# main.net
KiCad netlist of a schematic drawn in Altium Designer
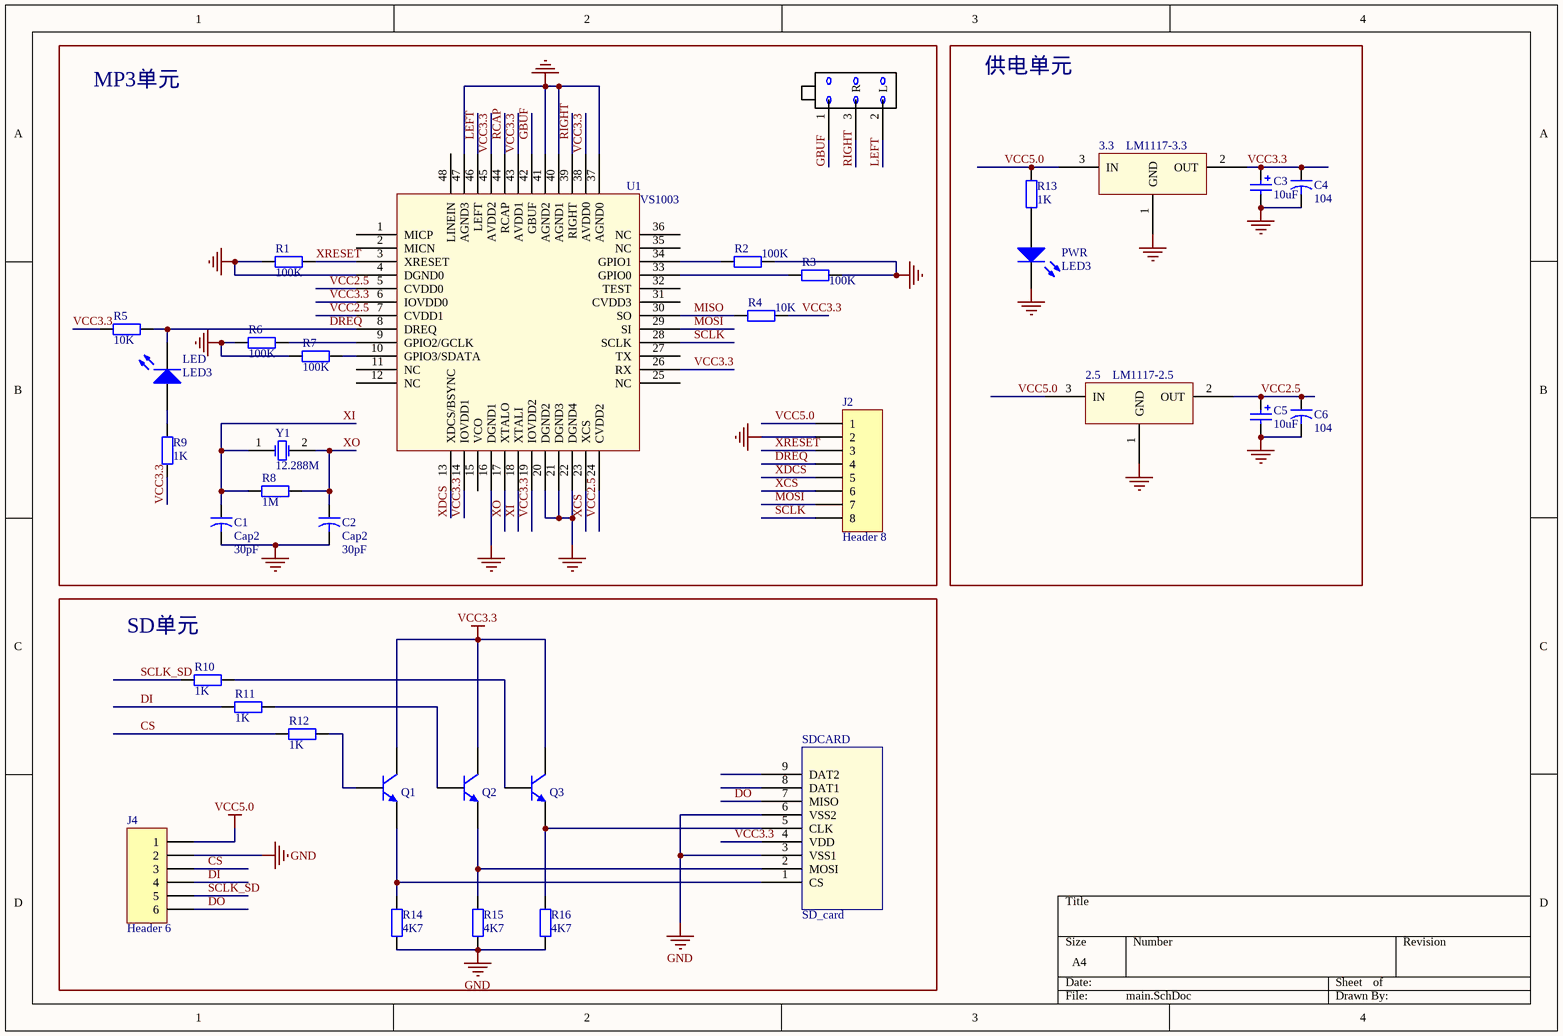
[diagram p0: main.SchDoc]

(export (version "E")
  (design (tool "Eeschema 10.0.6"))
  (components
    (comp (ref "2.5") (value "LM1117-2.5") (footprint "SOT223") (libsource (lib "kkk") (part "LM1117-3.3")))
    (comp (ref "3.3") (value "LM1117-3.3") (footprint "SOT223") (libsource (lib "kkk") (part "LM1117-3.3")))
    (comp (ref "C1")
      (value "Cap2")
      (footprint "C0805")
      (description "Capacitor")
      (fields (field (name "ALTIUM_VALUE") "30pF") (field (name "PUBLISHER") "Altium Limited"))
      (libsource (lib "Miscellaneous Devices") (part "Cap2"))
    )
    (comp (ref "C2")
      (value "Cap2")
      (footprint "C0805")
      (description "Capacitor")
      (fields (field (name "ALTIUM_VALUE") "30pF") (field (name "PUBLISHER") "Altium Limited"))
      (libsource (lib "Miscellaneous Devices") (part "Cap2"))
    )
    (comp (ref "C3")
      (value "10uF")
      (footprint "3528")
      (description "Polarized Capacitor (Surface Mount)")
      (fields (field (name "Comment") "Cap Pol3") (field (name "PUBLISHER") "Altium Limited"))
      (libsource (lib "Miscellaneous Devices") (part "Cap Pol3"))
    )
    (comp (ref "C4")
      (value "104")
      (footprint "C0805")
      (description "Capacitor")
      (fields (field (name "Comment") "Cap2") (field (name "PUBLISHER") "Altium Limited"))
      (libsource (lib "Miscellaneous Devices") (part "Cap2"))
    )
    (comp (ref "C5")
      (value "10uF")
      (footprint "3528")
      (description "Polarized Capacitor (Surface Mount)")
      (fields (field (name "Comment") "Cap Pol3") (field (name "PUBLISHER") "Altium Limited"))
      (libsource (lib "Miscellaneous Devices") (part "Cap Pol3"))
    )
    (comp (ref "C6")
      (value "104")
      (footprint "C0805")
      (description "Capacitor")
      (fields (field (name "Comment") "Cap2") (field (name "PUBLISHER") "Altium Limited"))
      (libsource (lib "Miscellaneous Devices") (part "Cap2"))
    )
    (comp (ref "J2")
      (value "Header 8")
      (footprint "HDR1X8")
      (description "Header, 8-Pin")
      (fields (field (name "PUBLISHER") "Altium Limited"))
      (libsource (lib "Miscellaneous Connectors") (part "Header 8"))
    )
    (comp (ref "J4")
      (value "Header 6")
      (footprint "HDR1X6")
      (description "Header, 6-Pin")
      (fields (field (name "PUBLISHER") "Altium Limited"))
      (libsource (lib "Miscellaneous Connectors") (part "Header 6"))
    )
    (comp (ref "LED")
      (value "LED3")
      (footprint "DSO-C2/D5.6")
      (description "Typical BLUE SiC LED")
      (fields (field (name "PUBLISHER") "Altium Limited"))
      (libsource (lib "Miscellaneous Devices") (part "LED3"))
    )
    (comp (ref "Phonejack")
      (value "Phonejack")
      (footprint "3.5mmphonejack")
      (libsource (lib "MyLib") (part "Phonejack"))
    )
    (comp (ref "PWR")
      (value "LED3")
      (footprint "DSO-C2/D5.6")
      (description "Typical BLUE SiC LED")
      (fields (field (name "PUBLISHER") "Altium Limited"))
      (libsource (lib "Miscellaneous Devices") (part "LED3"))
    )
    (comp (ref "Q1") (value "8050") (footprint "SOT-23") (libsource (lib "MyLib") (part "8050")))
    (comp (ref "Q2") (value "8050") (footprint "SOT-23") (libsource (lib "MyLib") (part "8050")))
    (comp (ref "Q3") (value "8050") (footprint "SOT-23") (libsource (lib "MyLib") (part "8050")))
    (comp (ref "R1")
      (value "100K")
      (footprint "C0805")
      (description "Resistor")
      (fields (field (name "Comment") "Res2") (field (name "PUBLISHER") "Altium Limited"))
      (libsource (lib "Miscellaneous Devices") (part "Res2"))
    )
    (comp (ref "R2")
      (value "100K")
      (footprint "C0805")
      (description "Resistor")
      (fields (field (name "Comment") "Res2") (field (name "PUBLISHER") "Altium Limited"))
      (libsource (lib "Miscellaneous Devices") (part "Res2"))
    )
    (comp (ref "R3")
      (value "100K")
      (footprint "C0805")
      (description "Resistor")
      (fields (field (name "Comment") "Res2") (field (name "PUBLISHER") "Altium Limited"))
      (libsource (lib "Miscellaneous Devices") (part "Res2"))
    )
    (comp (ref "R4")
      (value "10K")
      (footprint "C0805")
      (description "Resistor")
      (fields (field (name "Comment") "Res2") (field (name "PUBLISHER") "Altium Limited"))
      (libsource (lib "Miscellaneous Devices") (part "Res2"))
    )
    (comp (ref "R5")
      (value "10K")
      (footprint "C0805")
      (description "Resistor")
      (fields (field (name "Comment") "Res2") (field (name "PUBLISHER") "Altium Limited"))
      (libsource (lib "Miscellaneous Devices") (part "Res2"))
    )
    (comp (ref "R6")
      (value "100K")
      (footprint "C0805")
      (description "Resistor")
      (fields (field (name "Comment") "Res2") (field (name "PUBLISHER") "Altium Limited"))
      (libsource (lib "Miscellaneous Devices") (part "Res2"))
    )
    (comp (ref "R7")
      (value "100K")
      (footprint "C0805")
      (description "Resistor")
      (fields (field (name "Comment") "Res2") (field (name "PUBLISHER") "Altium Limited"))
      (libsource (lib "Miscellaneous Devices") (part "Res2"))
    )
    (comp (ref "R8")
      (value "1M")
      (footprint "C0805")
      (description "Resistor")
      (fields (field (name "Comment") "Res2") (field (name "PUBLISHER") "Altium Limited"))
      (libsource (lib "Miscellaneous Devices") (part "Res2"))
    )
    (comp (ref "R9")
      (value "1K")
      (footprint "C0805")
      (description "Resistor")
      (fields (field (name "Comment") "Res2") (field (name "PUBLISHER") "Altium Limited"))
      (libsource (lib "") (part "Res2_2"))
    )
    (comp (ref "R10")
      (value "1K")
      (footprint "C0805")
      (description "Resistor")
      (fields (field (name "Comment") "Res2") (field (name "PUBLISHER") "Altium Limited"))
      (libsource (lib "") (part "Res2_3"))
    )
    (comp (ref "R11")
      (value "1K")
      (footprint "C0805")
      (description "Resistor")
      (fields (field (name "Comment") "Res2") (field (name "PUBLISHER") "Altium Limited"))
      (libsource (lib "") (part "Res2_3"))
    )
    (comp (ref "R12")
      (value "1K")
      (footprint "C0805")
      (description "Resistor")
      (fields (field (name "Comment") "Res2") (field (name "PUBLISHER") "Altium Limited"))
      (libsource (lib "") (part "Res2_3"))
    )
    (comp (ref "R13")
      (value "1K")
      (footprint "C0805")
      (description "Resistor")
      (fields (field (name "Comment") "Res2") (field (name "PUBLISHER") "Altium Limited"))
      (libsource (lib "") (part "Res2_4"))
    )
    (comp (ref "R14")
      (value "4K7")
      (footprint "C0805")
      (description "Resistor")
      (fields (field (name "Comment") "Res2") (field (name "PUBLISHER") "Altium Limited"))
      (libsource (lib "") (part "Res2_1"))
    )
    (comp (ref "R15")
      (value "4K7")
      (footprint "C0805")
      (description "Resistor")
      (fields (field (name "Comment") "Res2") (field (name "PUBLISHER") "Altium Limited"))
      (libsource (lib "") (part "Res2_1"))
    )
    (comp (ref "R16")
      (value "4K7")
      (footprint "C0805")
      (description "Resistor")
      (fields (field (name "Comment") "Res2") (field (name "PUBLISHER") "Altium Limited"))
      (libsource (lib "") (part "Res2_1"))
    )
    (comp (ref "SDCARD") (value "SD_card") (footprint "SDCARD") (libsource (lib "kkk") (part "SD_card")))
    (comp (ref "U1") (value "VS1003") (footprint "LQFP-48") (libsource (lib "kkk") (part "VS1003")))
    (comp (ref "Y1")
      (value "12.288M")
      (footprint "XTAL")
      (description "Crystal Oscillator")
      (fields (field (name "PUBLISHER") "Altium Limited"))
      (libsource (lib "Miscellaneous Devices") (part "XTAL"))
    )
  )
  (nets
    (net (code "1") (name "/CS") (class "Default")
      (node (ref "J4") (pin "3") (pinfunction "3_3") (pintype "passive"))
      (node (ref "R12") (pin "1") (pinfunction "1_1") (pintype "passive"))
    )
    (net (code "2") (name "/DI") (class "Default")
      (node (ref "J4") (pin "4") (pinfunction "4_4") (pintype "passive"))
      (node (ref "R11") (pin "1") (pinfunction "1_1") (pintype "passive"))
    )
    (net (code "3") (name "/DO") (class "Default")
      (node (ref "J4") (pin "6") (pinfunction "6_6") (pintype "passive"))
      (node (ref "SDCARD") (pin "7") (pinfunction "MISO_7") (pintype "power_in"))
    )
    (net (code "4") (name "/DREQ") (class "Default")
      (node (ref "J2") (pin "4") (pinfunction "4_4") (pintype "passive"))
      (node (ref "LED") (pin "2") (pinfunction "K_2") (pintype "passive"))
      (node (ref "R5") (pin "2") (pinfunction "2_2") (pintype "passive"))
      (node (ref "U1") (pin "8") (pinfunction "DREQ_8") (pintype "passive"))
    )
    (net (code "5") (name "/GBUF") (class "Default")
      (node (ref "Phonejack") (pin "1") (pinfunction "GBUF_1") (pintype "passive"))
      (node (ref "U1") (pin "42") (pinfunction "GBUF_42") (pintype "passive"))
    )
    (net (code "6") (name "/LEFT") (class "Default")
      (node (ref "Phonejack") (pin "2") (pinfunction "L_2") (pintype "passive"))
      (node (ref "U1") (pin "46") (pinfunction "LEFT_46") (pintype "passive"))
    )
    (net (code "7") (name "/MISO") (class "Default")
      (node (ref "R4") (pin "1") (pinfunction "1_1") (pintype "passive"))
      (node (ref "U1") (pin "30") (pinfunction "SO_30") (pintype "passive"))
    )
    (net (code "8") (name "/MOSI") (class "Default")
      (node (ref "J2") (pin "7") (pinfunction "7_7") (pintype "passive"))
      (node (ref "U1") (pin "29") (pinfunction "SI_29") (pintype "passive"))
    )
    (net (code "9") (name "/RCAP") (class "Default")
      (node (ref "U1") (pin "44") (pinfunction "RCAP_44") (pintype "passive"))
    )
    (net (code "10") (name "/RIGHT") (class "Default")
      (node (ref "Phonejack") (pin "3") (pinfunction "R_3") (pintype "passive"))
      (node (ref "U1") (pin "39") (pinfunction "RIGHT_39") (pintype "passive"))
    )
    (net (code "11") (name "/SCLK") (class "Default")
      (node (ref "J2") (pin "8") (pinfunction "8_8") (pintype "passive"))
      (node (ref "U1") (pin "28") (pinfunction "SCLK_28") (pintype "passive"))
    )
    (net (code "12") (name "/SCLK_SD") (class "Default")
      (node (ref "J4") (pin "5") (pinfunction "5_5") (pintype "passive"))
      (node (ref "R10") (pin "1") (pinfunction "1_1") (pintype "passive"))
    )
    (net (code "13") (name "/VCC2.5") (class "Default")
      (node (ref "2.5") (pin "2") (pinfunction "OUT_2") (pintype "passive"))
      (node (ref "C5") (pin "1") (pinfunction "1_1") (pintype "passive"))
      (node (ref "C6") (pin "1") (pinfunction "1_1") (pintype "passive"))
      (node (ref "U1") (pin "24") (pinfunction "CVDD2_24") (pintype "passive"))
      (node (ref "U1") (pin "5") (pinfunction "CVDD0_5") (pintype "passive"))
      (node (ref "U1") (pin "7") (pinfunction "CVDD1_7") (pintype "passive"))
    )
    (net (code "14") (name "/XCS") (class "Default")
      (node (ref "J2") (pin "6") (pinfunction "6_6") (pintype "passive"))
      (node (ref "U1") (pin "23") (pinfunction "XCS_23") (pintype "passive"))
    )
    (net (code "15") (name "/XDCS") (class "Default")
      (node (ref "J2") (pin "5") (pinfunction "5_5") (pintype "passive"))
      (node (ref "U1") (pin "13") (pinfunction "XDCS/BSYNC_13") (pintype "passive"))
    )
    (net (code "16") (name "/XI") (class "Default")
      (node (ref "C1") (pin "1") (pinfunction "1_1") (pintype "passive"))
      (node (ref "R8") (pin "1") (pinfunction "1_1") (pintype "passive"))
      (node (ref "U1") (pin "18") (pinfunction "XTALI_18") (pintype "passive"))
      (node (ref "Y1") (pin "1") (pinfunction "OSC1_1") (pintype "passive"))
    )
    (net (code "17") (name "/XO") (class "Default")
      (node (ref "C2") (pin "1") (pinfunction "1_1") (pintype "passive"))
      (node (ref "R8") (pin "2") (pinfunction "2_2") (pintype "passive"))
      (node (ref "U1") (pin "17") (pinfunction "XTALO_17") (pintype "passive"))
      (node (ref "Y1") (pin "2") (pinfunction "OSC2_2") (pintype "passive"))
    )
    (net (code "18") (name "/XRESET") (class "Default")
      (node (ref "J2") (pin "3") (pinfunction "3_3") (pintype "passive"))
      (node (ref "R1") (pin "2") (pinfunction "2_2") (pintype "passive"))
      (node (ref "U1") (pin "3") (pinfunction "XRESET_3") (pintype "passive"))
    )
    (net (code "19") (name "GND") (class "Default")
      (node (ref "2.5") (pin "1") (pinfunction "GND_1") (pintype "passive"))
      (node (ref "3.3") (pin "1") (pinfunction "GND_1") (pintype "passive"))
      (node (ref "C1") (pin "2") (pinfunction "2_2") (pintype "passive"))
      (node (ref "C2") (pin "2") (pinfunction "2_2") (pintype "passive"))
      (node (ref "C3") (pin "2") (pinfunction "2_2") (pintype "passive"))
      (node (ref "C4") (pin "2") (pinfunction "2_2") (pintype "passive"))
      (node (ref "C5") (pin "2") (pinfunction "2_2") (pintype "passive"))
      (node (ref "C6") (pin "2") (pinfunction "2_2") (pintype "passive"))
      (node (ref "J2") (pin "2") (pinfunction "2_2") (pintype "passive"))
      (node (ref "J4") (pin "2") (pinfunction "2_2") (pintype "passive"))
      (node (ref "PWR") (pin "2") (pinfunction "K_2") (pintype "passive"))
      (node (ref "R1") (pin "1") (pinfunction "1_1") (pintype "passive"))
      (node (ref "R14") (pin "1") (pinfunction "1_1") (pintype "passive"))
      (node (ref "R15") (pin "1") (pinfunction "1_1") (pintype "passive"))
      (node (ref "R16") (pin "1") (pinfunction "1_1") (pintype "passive"))
      (node (ref "R2") (pin "2") (pinfunction "2_2") (pintype "passive"))
      (node (ref "R3") (pin "2") (pinfunction "2_2") (pintype "passive"))
      (node (ref "R6") (pin "1") (pinfunction "1_1") (pintype "passive"))
      (node (ref "R7") (pin "1") (pinfunction "1_1") (pintype "passive"))
      (node (ref "SDCARD") (pin "3") (pinfunction "VSS1_3") (pintype "power_in"))
      (node (ref "SDCARD") (pin "6") (pinfunction "VSS2_6") (pintype "power_in"))
      (node (ref "U1") (pin "16") (pinfunction "DGND1_16") (pintype "passive"))
      (node (ref "U1") (pin "20") (pinfunction "DGND2_20") (pintype "passive"))
      (node (ref "U1") (pin "21") (pinfunction "DGND3_21") (pintype "passive"))
      (node (ref "U1") (pin "22") (pinfunction "DGND4_22") (pintype "passive"))
      (node (ref "U1") (pin "37") (pinfunction "AGND0_37") (pintype "passive"))
      (node (ref "U1") (pin "4") (pinfunction "DGND0_4") (pintype "passive"))
      (node (ref "U1") (pin "40") (pinfunction "AGND1_40") (pintype "passive"))
      (node (ref "U1") (pin "41") (pinfunction "AGND2_41") (pintype "passive"))
      (node (ref "U1") (pin "47") (pinfunction "AGND3_47") (pintype "passive"))
    )
    (net (code "20") (name "Net-(LED-A)") (class "Default")
      (node (ref "LED") (pin "1") (pinfunction "A_1") (pintype "passive"))
      (node (ref "R9") (pin "2") (pinfunction "2_2") (pintype "passive"))
    )
    (net (code "21") (name "Net-(PWR-A)") (class "Default")
      (node (ref "PWR") (pin "1") (pinfunction "A_1") (pintype "passive"))
      (node (ref "R13") (pin "2") (pinfunction "2_2") (pintype "passive"))
    )
    (net (code "22") (name "Net-(Q1-B)") (class "Default")
      (node (ref "Q1") (pin "1") (pinfunction "B_1") (pintype "passive"))
      (node (ref "R12") (pin "2") (pinfunction "2_2") (pintype "passive"))
    )
    (net (code "23") (name "Net-(Q1-E)") (class "Default")
      (node (ref "Q1") (pin "2") (pinfunction "E_2") (pintype "passive"))
      (node (ref "R14") (pin "2") (pinfunction "2_2") (pintype "passive"))
      (node (ref "SDCARD") (pin "1") (pinfunction "CS_1") (pintype "power_in"))
    )
    (net (code "24") (name "Net-(Q2-B)") (class "Default")
      (node (ref "Q2") (pin "1") (pinfunction "B_1") (pintype "passive"))
      (node (ref "R11") (pin "2") (pinfunction "2_2") (pintype "passive"))
    )
    (net (code "25") (name "Net-(Q2-E)") (class "Default")
      (node (ref "Q2") (pin "2") (pinfunction "E_2") (pintype "passive"))
      (node (ref "R15") (pin "2") (pinfunction "2_2") (pintype "passive"))
      (node (ref "SDCARD") (pin "2") (pinfunction "MOSI_2") (pintype "power_in"))
    )
    (net (code "26") (name "Net-(Q3-B)") (class "Default")
      (node (ref "Q3") (pin "1") (pinfunction "B_1") (pintype "passive"))
      (node (ref "R10") (pin "2") (pinfunction "2_2") (pintype "passive"))
    )
    (net (code "27") (name "Net-(Q3-E)") (class "Default")
      (node (ref "Q3") (pin "2") (pinfunction "E_2") (pintype "passive"))
      (node (ref "R16") (pin "2") (pinfunction "2_2") (pintype "passive"))
      (node (ref "SDCARD") (pin "5") (pinfunction "CLK_5") (pintype "power_in"))
    )
    (net (code "28") (name "Net-(U1-GPIO0)") (class "Default")
      (node (ref "R3") (pin "1") (pinfunction "1_1") (pintype "passive"))
      (node (ref "U1") (pin "33") (pinfunction "GPIO0_33") (pintype "passive"))
    )
    (net (code "29") (name "Net-(U1-GPIO1)") (class "Default")
      (node (ref "R2") (pin "1") (pinfunction "1_1") (pintype "passive"))
      (node (ref "U1") (pin "34") (pinfunction "GPIO1_34") (pintype "passive"))
    )
    (net (code "30") (name "Net-(U1-GPIO2{slash}GCLK)") (class "Default")
      (node (ref "R6") (pin "2") (pinfunction "2_2") (pintype "passive"))
      (node (ref "U1") (pin "9") (pinfunction "GPIO2/GCLK_9") (pintype "passive"))
    )
    (net (code "31") (name "Net-(U1-GPIO3{slash}SDATA)") (class "Default")
      (node (ref "R7") (pin "2") (pinfunction "2_2") (pintype "passive"))
      (node (ref "U1") (pin "10") (pinfunction "GPIO3/SDATA_10") (pintype "passive"))
    )
    (net (code "32") (name "VCC3.3") (class "Default")
      (node (ref "3.3") (pin "2") (pinfunction "OUT_2") (pintype "passive"))
      (node (ref "C3") (pin "1") (pinfunction "1_1") (pintype "passive"))
      (node (ref "C4") (pin "1") (pinfunction "1_1") (pintype "passive"))
      (node (ref "Q1") (pin "3") (pinfunction "C_3") (pintype "passive"))
      (node (ref "Q2") (pin "3") (pinfunction "C_3") (pintype "passive"))
      (node (ref "Q3") (pin "3") (pinfunction "C_3") (pintype "passive"))
      (node (ref "R4") (pin "2") (pinfunction "2_2") (pintype "passive"))
      (node (ref "R5") (pin "1") (pinfunction "1_1") (pintype "passive"))
      (node (ref "R9") (pin "1") (pinfunction "1_1") (pintype "passive"))
      (node (ref "SDCARD") (pin "4") (pinfunction "VDD_4") (pintype "power_in"))
      (node (ref "U1") (pin "14") (pinfunction "IOVDD1_14") (pintype "passive"))
      (node (ref "U1") (pin "19") (pinfunction "IOVDD2_19") (pintype "passive"))
      (node (ref "U1") (pin "26") (pinfunction "RX_26") (pintype "passive"))
      (node (ref "U1") (pin "38") (pinfunction "AVDD0_38") (pintype "passive"))
      (node (ref "U1") (pin "43") (pinfunction "AVDD1_43") (pintype "passive"))
      (node (ref "U1") (pin "45") (pinfunction "AVDD2_45") (pintype "passive"))
      (node (ref "U1") (pin "6") (pinfunction "IOVDD0_6") (pintype "passive"))
    )
    (net (code "33") (name "VCC5.0") (class "Default")
      (node (ref "2.5") (pin "3") (pinfunction "IN_3") (pintype "passive"))
      (node (ref "3.3") (pin "3") (pinfunction "IN_3") (pintype "passive"))
      (node (ref "J2") (pin "1") (pinfunction "1_1") (pintype "passive"))
      (node (ref "J4") (pin "1") (pinfunction "1_1") (pintype "passive"))
      (node (ref "R13") (pin "1") (pinfunction "1_1") (pintype "passive"))
    )
    (net (code "34") (name "unconnected-(SDCARD-DAT1-Pad8)") (class "Default")
      (node (ref "SDCARD") (pin "8") (pinfunction "DAT1_8") (pintype "power_in"))
    )
    (net (code "35") (name "unconnected-(SDCARD-DAT2-Pad9)") (class "Default")
      (node (ref "SDCARD") (pin "9") (pinfunction "DAT2_9") (pintype "power_in"))
    )
    (net (code "36") (name "unconnected-(U1-CVDD3-Pad31)") (class "Default")
      (node (ref "U1") (pin "31") (pinfunction "CVDD3_31") (pintype "passive"))
    )
    (net (code "37") (name "unconnected-(U1-LINEIN-Pad48)") (class "Default")
      (node (ref "U1") (pin "48") (pinfunction "LINEIN_48") (pintype "passive"))
    )
    (net (code "38") (name "unconnected-(U1-MICN-Pad2)") (class "Default")
      (node (ref "U1") (pin "2") (pinfunction "MICN_2") (pintype "passive"))
    )
    (net (code "39") (name "unconnected-(U1-MICP-Pad1)") (class "Default")
      (node (ref "U1") (pin "1") (pinfunction "MICP_1") (pintype "passive"))
    )
    (net (code "40") (name "unconnected-(U1-NC-Pad11)") (class "Default")
      (node (ref "U1") (pin "11") (pinfunction "NC_11") (pintype "passive"))
    )
    (net (code "41") (name "unconnected-(U1-NC-Pad12)") (class "Default")
      (node (ref "U1") (pin "12") (pinfunction "NC_12") (pintype "passive"))
    )
    (net (code "42") (name "unconnected-(U1-NC-Pad25)") (class "Default")
      (node (ref "U1") (pin "25") (pinfunction "NC_25") (pintype "passive"))
    )
    (net (code "43") (name "unconnected-(U1-NC-Pad35)") (class "Default")
      (node (ref "U1") (pin "35") (pinfunction "NC_35") (pintype "passive"))
    )
    (net (code "44") (name "unconnected-(U1-NC-Pad36)") (class "Default")
      (node (ref "U1") (pin "36") (pinfunction "NC_36") (pintype "passive"))
    )
    (net (code "45") (name "unconnected-(U1-TEST-Pad32)") (class "Default")
      (node (ref "U1") (pin "32") (pinfunction "TEST_32") (pintype "passive"))
    )
    (net (code "46") (name "unconnected-(U1-TX-Pad27)") (class "Default")
      (node (ref "U1") (pin "27") (pinfunction "TX_27") (pintype "passive"))
    )
    (net (code "47") (name "unconnected-(U1-VCO-Pad15)") (class "Default")
      (node (ref "U1") (pin "15") (pinfunction "VCO_15") (pintype "passive"))
    )
  )
)
